# Killswitch.net
KiCad netlist of a schematic drawn in EAGLE
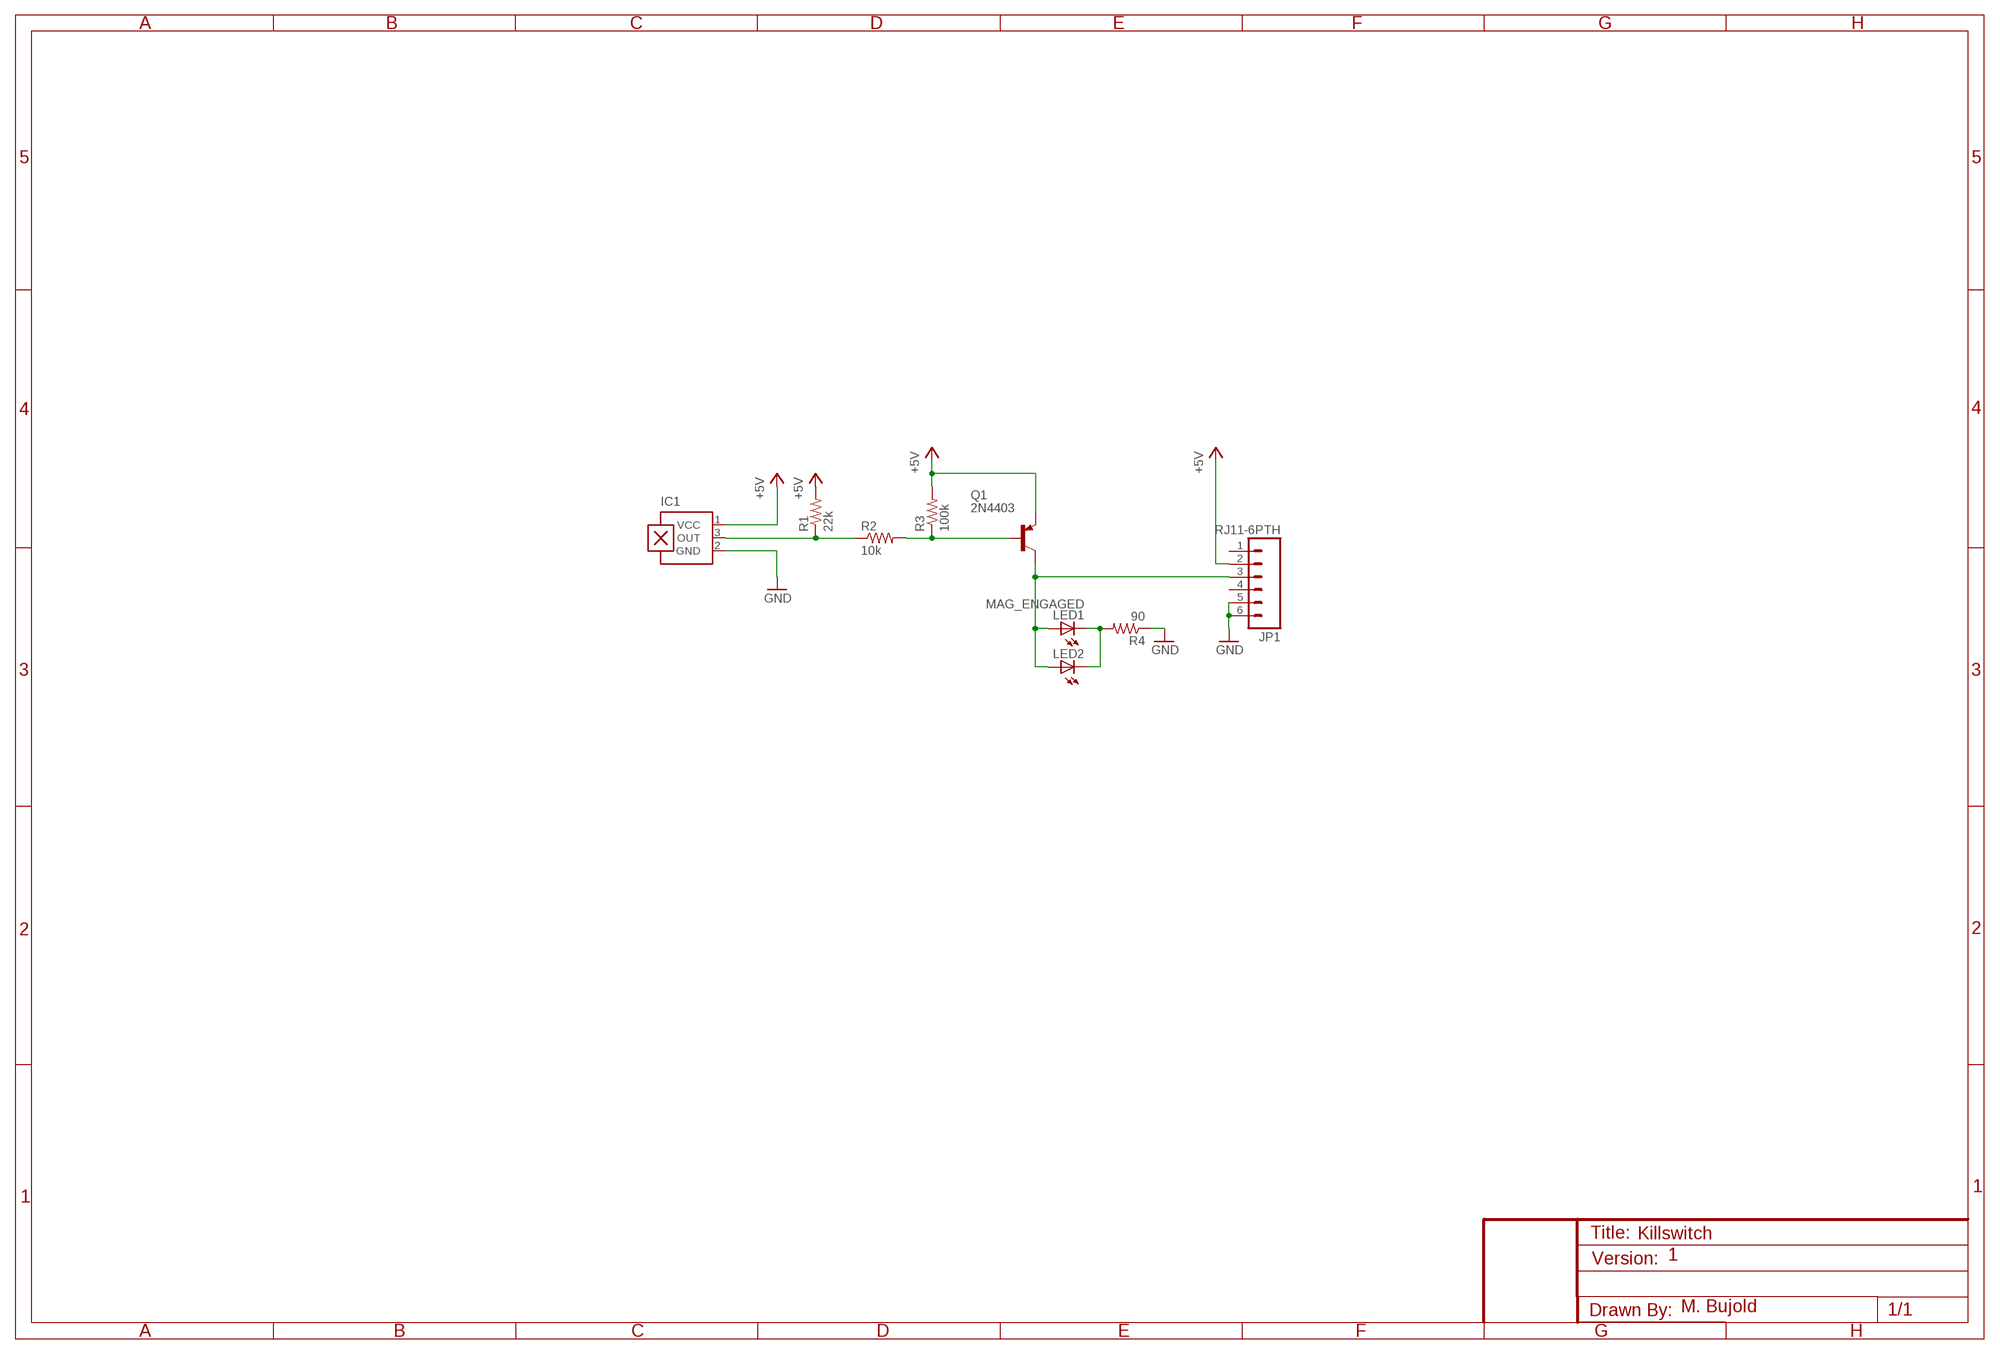
[diagram p0: schematic, sheet 1]

(export (version "E")
  (design (tool "Eeschema 10.0.6"))
  (components
    (comp (ref "IC1")
      (value "A1384UA")
      (footprint "eagle-import:SIP3-UA")
      (fields (field (name "MPN") "A1384LUA-T"))
      (libsource (lib "eagle-import") (part "A13?UA84"))
    )
    (comp (ref "JP1")
      (value "RJ11-6PTH")
      (footprint "eagle-import:RJ11-6")
      (libsource (lib "eagle-import") (part "RJ11-6PTH"))
    )
    (comp (ref "LED1")
      (value "MAG_ENGAGED")
      (footprint "eagle-import:CHIPLED_1206")
      (libsource (lib "eagle-import") (part "LEDCHIPLED_1206"))
    )
    (comp (ref "LED2")
      (value "LED3MM")
      (footprint "eagle-import:LED3MM")
      (libsource (lib "eagle-import") (part "LED3MM"))
    )
    (comp (ref "Q1")
      (value "2N4403")
      (footprint "eagle-import:TO92")
      (libsource (lib "eagle-import") (part "2N3906"))
    )
    (comp (ref "R1")
      (value "22k")
      (footprint "eagle-import:1206")
      (libsource (lib "eagle-import") (part "RESISTOR1206"))
    )
    (comp (ref "R2")
      (value "10k")
      (footprint "eagle-import:1206")
      (libsource (lib "eagle-import") (part "RESISTOR1206"))
    )
    (comp (ref "R3")
      (value "100k")
      (footprint "eagle-import:1206")
      (libsource (lib "eagle-import") (part "RESISTOR1206"))
    )
    (comp (ref "R4")
      (value "90")
      (footprint "eagle-import:1206")
      (libsource (lib "eagle-import") (part "RESISTOR1206"))
    )
  )
  (nets
    (net (code "1") (name "+5V") (class "Default")
      (node (ref "IC1") (pin "1") (pinfunction "VCC_1") (pintype "power_in"))
      (node (ref "JP1") (pin "2") (pinfunction "2_2") (pintype "passive"))
      (node (ref "Q1") (pin "3") (pinfunction "E_3") (pintype "passive"))
      (node (ref "R1") (pin "2") (pinfunction "2_2") (pintype "passive"))
      (node (ref "R3") (pin "2") (pinfunction "2_2") (pintype "passive"))
    )
    (net (code "2") (name "GND") (class "Default")
      (node (ref "IC1") (pin "2") (pinfunction "GND_2") (pintype "power_in"))
      (node (ref "JP1") (pin "5") (pinfunction "5_5") (pintype "passive"))
      (node (ref "JP1") (pin "6") (pinfunction "6_6") (pintype "passive"))
      (node (ref "R4") (pin "1") (pinfunction "1_1") (pintype "passive"))
    )
    (net (code "3") (name "Net-(IC1-OUT)") (class "Default")
      (node (ref "IC1") (pin "3") (pinfunction "OUT_3") (pintype "output"))
      (node (ref "R1") (pin "1") (pinfunction "1_1") (pintype "passive"))
      (node (ref "R2") (pin "1") (pinfunction "1_1") (pintype "passive"))
    )
    (net (code "4") (name "Net-(LED2-C)") (class "Default")
      (node (ref "LED1") (pin "C") (pinfunction "C_C") (pintype "passive"))
      (node (ref "LED2") (pin "K") (pinfunction "C_K") (pintype "passive"))
      (node (ref "R4") (pin "2") (pinfunction "2_2") (pintype "passive"))
    )
    (net (code "5") (name "Net-(Q1-B)") (class "Default")
      (node (ref "Q1") (pin "2") (pinfunction "B_2") (pintype "passive"))
      (node (ref "R2") (pin "2") (pinfunction "2_2") (pintype "passive"))
      (node (ref "R3") (pin "1") (pinfunction "1_1") (pintype "passive"))
    )
    (net (code "6") (name "Net-(Q1-C)") (class "Default")
      (node (ref "JP1") (pin "3") (pinfunction "3_3") (pintype "passive"))
      (node (ref "LED1") (pin "A") (pinfunction "A_A") (pintype "passive"))
      (node (ref "LED2") (pin "A") (pinfunction "A_A") (pintype "passive"))
      (node (ref "Q1") (pin "1") (pinfunction "C_1") (pintype "passive"))
    )
    (net (code "7") (name "unconnected-(JP1-Pad1)") (class "Default")
      (node (ref "JP1") (pin "1") (pinfunction "1_1") (pintype "passive"))
    )
    (net (code "8") (name "unconnected-(JP1-Pad4)") (class "Default")
      (node (ref "JP1") (pin "4") (pinfunction "4_4") (pintype "passive"))
    )
  )
)
